# mem.net
KiCad netlist of a schematic drawn in Altium Designer
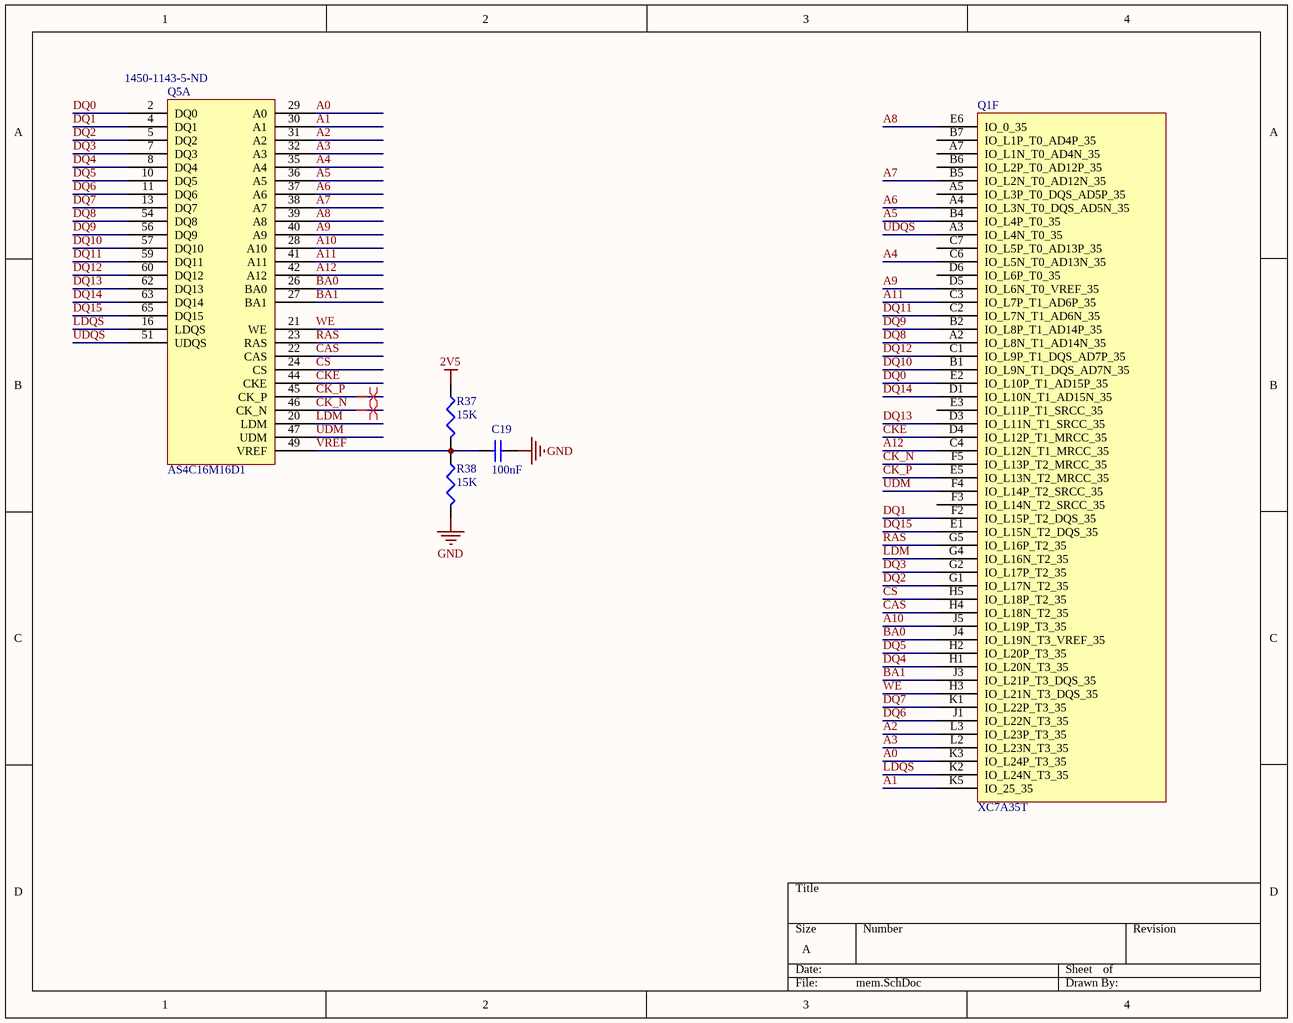
[diagram p0: mem.SchDoc]

(export (version "E")
  (design (tool "Eeschema 10.0.6"))
  (components
    (comp (ref "C19")
      (value "100nF")
      (footprint "CAPC1005X06L")
      (description "Capacitor")
      (fields (field (name "Comment") "Cap") (field (name "PUBLISHER") "Altium Limited"))
      (libsource (lib "Miscellaneous Devices") (part "Cap"))
    )
    (comp (ref "Q1") (value "XC7A35T") (libsource (lib "schlib") (part "XC7A35T")))
    (comp (ref "Q5")
      (value "AS4C16M16D1")
      (footprint "TSOP65P1180X120-66N")
      (fields (field (name "SUPPLIER PART NUMBER 1") "1450-1143-5-ND"))
      (libsource (lib "schlib") (part "DDR256"))
    )
    (comp (ref "R37")
      (value "15K")
      (footprint "CAPC1608X90N")
      (description "Resistor")
      (fields (field (name "Comment") "Res3") (field (name "PUBLISHER") "Altium Limited"))
      (libsource (lib "Miscellaneous Devices") (part "Res3"))
    )
    (comp (ref "R38")
      (value "15K")
      (footprint "CAPC1608X90N")
      (description "Resistor")
      (fields (field (name "Comment") "Res3") (field (name "PUBLISHER") "Altium Limited"))
      (libsource (lib "Miscellaneous Devices") (part "Res3"))
    )
  )
  (nets
    (net (code "1") (name "/A0") (class "Default")
      (node (ref "Q1") (pin "K3") (pinfunction "IO_L24P_T3_35_K3") (pintype "passive"))
      (node (ref "Q5") (pin "29") (pinfunction "A0_29") (pintype "passive"))
    )
    (net (code "2") (name "/A1") (class "Default")
      (node (ref "Q1") (pin "K5") (pinfunction "IO_25_35_K5") (pintype "passive"))
      (node (ref "Q5") (pin "30") (pinfunction "A1_30") (pintype "passive"))
    )
    (net (code "3") (name "/A2") (class "Default")
      (node (ref "Q1") (pin "L3") (pinfunction "IO_L23P_T3_35_L3") (pintype "passive"))
      (node (ref "Q5") (pin "31") (pinfunction "A2_31") (pintype "passive"))
    )
    (net (code "4") (name "/A3") (class "Default")
      (node (ref "Q1") (pin "L2") (pinfunction "IO_L23N_T3_35_L2") (pintype "passive"))
      (node (ref "Q5") (pin "32") (pinfunction "A3_32") (pintype "passive"))
    )
    (net (code "5") (name "/A4") (class "Default")
      (node (ref "Q1") (pin "C6") (pinfunction "IO_L5N_T0_AD13N_35_C6") (pintype "passive"))
      (node (ref "Q5") (pin "35") (pinfunction "A4_35") (pintype "passive"))
    )
    (net (code "6") (name "/A5") (class "Default")
      (node (ref "Q1") (pin "B4") (pinfunction "IO_L4P_T0_35_B4") (pintype "passive"))
      (node (ref "Q5") (pin "36") (pinfunction "A5_36") (pintype "passive"))
    )
    (net (code "7") (name "/A6") (class "Default")
      (node (ref "Q1") (pin "A4") (pinfunction "IO_L3N_T0_DQS_AD5N_35_A4") (pintype "passive"))
      (node (ref "Q5") (pin "37") (pinfunction "A6_37") (pintype "passive"))
    )
    (net (code "8") (name "/A7") (class "Default")
      (node (ref "Q1") (pin "B5") (pinfunction "IO_L2N_T0_AD12N_35_B5") (pintype "passive"))
      (node (ref "Q5") (pin "38") (pinfunction "A7_38") (pintype "passive"))
    )
    (net (code "9") (name "/A8") (class "Default")
      (node (ref "Q1") (pin "E6") (pinfunction "IO_0_35_E6") (pintype "passive"))
      (node (ref "Q5") (pin "39") (pinfunction "A8_39") (pintype "passive"))
    )
    (net (code "10") (name "/A9") (class "Default")
      (node (ref "Q1") (pin "D5") (pinfunction "IO_L6N_T0_VREF_35_D5") (pintype "passive"))
      (node (ref "Q5") (pin "40") (pinfunction "A9_40") (pintype "passive"))
    )
    (net (code "11") (name "/A10") (class "Default")
      (node (ref "Q1") (pin "J5") (pinfunction "IO_L19P_T3_35_J5") (pintype "passive"))
      (node (ref "Q5") (pin "28") (pinfunction "A10_28") (pintype "passive"))
    )
    (net (code "12") (name "/A11") (class "Default")
      (node (ref "Q1") (pin "C3") (pinfunction "IO_L7P_T1_AD6P_35_C3") (pintype "passive"))
      (node (ref "Q5") (pin "41") (pinfunction "A11_41") (pintype "passive"))
    )
    (net (code "13") (name "/A12") (class "Default")
      (node (ref "Q1") (pin "C4") (pinfunction "IO_L12N_T1_MRCC_35_C4") (pintype "passive"))
      (node (ref "Q5") (pin "42") (pinfunction "A12_42") (pintype "passive"))
    )
    (net (code "14") (name "/BA0") (class "Default")
      (node (ref "Q1") (pin "J4") (pinfunction "IO_L19N_T3_VREF_35_J4") (pintype "passive"))
      (node (ref "Q5") (pin "26") (pinfunction "BA0_26") (pintype "passive"))
    )
    (net (code "15") (name "/BA1") (class "Default")
      (node (ref "Q1") (pin "J3") (pinfunction "IO_L21P_T3_DQS_35_J3") (pintype "passive"))
      (node (ref "Q5") (pin "27") (pinfunction "BA1_27") (pintype "passive"))
    )
    (net (code "16") (name "/CAS") (class "Default")
      (node (ref "Q1") (pin "H4") (pinfunction "IO_L18N_T2_35_H4") (pintype "passive"))
      (node (ref "Q5") (pin "22") (pinfunction "CAS_22") (pintype "passive"))
    )
    (net (code "17") (name "/CKE") (class "Default")
      (node (ref "Q1") (pin "D4") (pinfunction "IO_L12P_T1_MRCC_35_D4") (pintype "passive"))
      (node (ref "Q5") (pin "44") (pinfunction "CKE_44") (pintype "passive"))
    )
    (net (code "18") (name "/CK_N") (class "Default")
      (node (ref "Q1") (pin "F5") (pinfunction "IO_L13P_T2_MRCC_35_F5") (pintype "passive"))
      (node (ref "Q5") (pin "46") (pinfunction "CK_N_46") (pintype "passive"))
    )
    (net (code "19") (name "/CK_P") (class "Default")
      (node (ref "Q1") (pin "E5") (pinfunction "IO_L13N_T2_MRCC_35_E5") (pintype "passive"))
      (node (ref "Q5") (pin "45") (pinfunction "CK_P_45") (pintype "passive"))
    )
    (net (code "20") (name "/CS") (class "Default")
      (node (ref "Q1") (pin "H5") (pinfunction "IO_L18P_T2_35_H5") (pintype "passive"))
      (node (ref "Q5") (pin "24") (pinfunction "CS_24") (pintype "passive"))
    )
    (net (code "21") (name "/DQ0") (class "Default")
      (node (ref "Q1") (pin "E2") (pinfunction "IO_L10P_T1_AD15P_35_E2") (pintype "passive"))
      (node (ref "Q5") (pin "2") (pinfunction "DQ0_2") (pintype "passive"))
    )
    (net (code "22") (name "/DQ1") (class "Default")
      (node (ref "Q1") (pin "F2") (pinfunction "IO_L15P_T2_DQS_35_F2") (pintype "passive"))
      (node (ref "Q5") (pin "4") (pinfunction "DQ1_4") (pintype "passive"))
    )
    (net (code "23") (name "/DQ2") (class "Default")
      (node (ref "Q1") (pin "G1") (pinfunction "IO_L17N_T2_35_G1") (pintype "passive"))
      (node (ref "Q5") (pin "5") (pinfunction "DQ2_5") (pintype "passive"))
    )
    (net (code "24") (name "/DQ3") (class "Default")
      (node (ref "Q1") (pin "G2") (pinfunction "IO_L17P_T2_35_G2") (pintype "passive"))
      (node (ref "Q5") (pin "7") (pinfunction "DQ3_7") (pintype "passive"))
    )
    (net (code "25") (name "/DQ4") (class "Default")
      (node (ref "Q1") (pin "H1") (pinfunction "IO_L20N_T3_35_H1") (pintype "passive"))
      (node (ref "Q5") (pin "8") (pinfunction "DQ4_8") (pintype "passive"))
    )
    (net (code "26") (name "/DQ5") (class "Default")
      (node (ref "Q1") (pin "H2") (pinfunction "IO_L20P_T3_35_H2") (pintype "passive"))
      (node (ref "Q5") (pin "10") (pinfunction "DQ5_10") (pintype "passive"))
    )
    (net (code "27") (name "/DQ6") (class "Default")
      (node (ref "Q1") (pin "J1") (pinfunction "IO_L22N_T3_35_J1") (pintype "passive"))
      (node (ref "Q5") (pin "11") (pinfunction "DQ6_11") (pintype "passive"))
    )
    (net (code "28") (name "/DQ7") (class "Default")
      (node (ref "Q1") (pin "K1") (pinfunction "IO_L22P_T3_35_K1") (pintype "passive"))
      (node (ref "Q5") (pin "13") (pinfunction "DQ7_13") (pintype "passive"))
    )
    (net (code "29") (name "/DQ8") (class "Default")
      (node (ref "Q1") (pin "A2") (pinfunction "IO_L8N_T1_AD14N_35_A2") (pintype "passive"))
      (node (ref "Q5") (pin "54") (pinfunction "DQ8_54") (pintype "passive"))
    )
    (net (code "30") (name "/DQ9") (class "Default")
      (node (ref "Q1") (pin "B2") (pinfunction "IO_L8P_T1_AD14P_35_B2") (pintype "passive"))
      (node (ref "Q5") (pin "56") (pinfunction "DQ9_56") (pintype "passive"))
    )
    (net (code "31") (name "/DQ10") (class "Default")
      (node (ref "Q1") (pin "B1") (pinfunction "IO_L9N_T1_DQS_AD7N_35_B1") (pintype "passive"))
      (node (ref "Q5") (pin "57") (pinfunction "DQ10_57") (pintype "passive"))
    )
    (net (code "32") (name "/DQ11") (class "Default")
      (node (ref "Q1") (pin "C2") (pinfunction "IO_L7N_T1_AD6N_35_C2") (pintype "passive"))
      (node (ref "Q5") (pin "59") (pinfunction "DQ11_59") (pintype "passive"))
    )
    (net (code "33") (name "/DQ12") (class "Default")
      (node (ref "Q1") (pin "C1") (pinfunction "IO_L9P_T1_DQS_AD7P_35_C1") (pintype "passive"))
      (node (ref "Q5") (pin "60") (pinfunction "DQ12_60") (pintype "passive"))
    )
    (net (code "34") (name "/DQ13") (class "Default")
      (node (ref "Q1") (pin "D3") (pinfunction "IO_L11N_T1_SRCC_35_D3") (pintype "passive"))
      (node (ref "Q5") (pin "62") (pinfunction "DQ13_62") (pintype "passive"))
    )
    (net (code "35") (name "/DQ14") (class "Default")
      (node (ref "Q1") (pin "D1") (pinfunction "IO_L10N_T1_AD15N_35_D1") (pintype "passive"))
      (node (ref "Q5") (pin "63") (pinfunction "DQ14_63") (pintype "passive"))
    )
    (net (code "36") (name "/DQ15") (class "Default")
      (node (ref "Q1") (pin "E1") (pinfunction "IO_L15N_T2_DQS_35_E1") (pintype "passive"))
      (node (ref "Q5") (pin "65") (pinfunction "DQ15_65") (pintype "passive"))
    )
    (net (code "37") (name "/LDM") (class "Default")
      (node (ref "Q1") (pin "G4") (pinfunction "IO_L16N_T2_35_G4") (pintype "passive"))
      (node (ref "Q5") (pin "20") (pinfunction "LDM_20") (pintype "passive"))
    )
    (net (code "38") (name "/LDQS") (class "Default")
      (node (ref "Q1") (pin "K2") (pinfunction "IO_L24N_T3_35_K2") (pintype "passive"))
      (node (ref "Q5") (pin "16") (pinfunction "LDQS_16") (pintype "passive"))
    )
    (net (code "39") (name "/RAS") (class "Default")
      (node (ref "Q1") (pin "G5") (pinfunction "IO_L16P_T2_35_G5") (pintype "passive"))
      (node (ref "Q5") (pin "23") (pinfunction "RAS_23") (pintype "passive"))
    )
    (net (code "40") (name "/UDM") (class "Default")
      (node (ref "Q1") (pin "F4") (pinfunction "IO_L14P_T2_SRCC_35_F4") (pintype "passive"))
      (node (ref "Q5") (pin "47") (pinfunction "UDM_47") (pintype "passive"))
    )
    (net (code "41") (name "/UDQS") (class "Default")
      (node (ref "Q1") (pin "A3") (pinfunction "IO_L4N_T0_35_A3") (pintype "passive"))
      (node (ref "Q5") (pin "51") (pinfunction "UDQS_51") (pintype "passive"))
    )
    (net (code "42") (name "/VREF") (class "Default")
      (node (ref "C19") (pin "1") (pinfunction "1_1") (pintype "passive"))
      (node (ref "Q5") (pin "49") (pinfunction "VREF_49") (pintype "passive"))
      (node (ref "R37") (pin "2") (pinfunction "2_2") (pintype "passive"))
      (node (ref "R38") (pin "1") (pinfunction "1_1") (pintype "passive"))
    )
    (net (code "43") (name "/WE") (class "Default")
      (node (ref "Q1") (pin "H3") (pinfunction "IO_L21N_T3_DQS_35_H3") (pintype "passive"))
      (node (ref "Q5") (pin "21") (pinfunction "WE_21") (pintype "passive"))
    )
    (net (code "44") (name "2V5") (class "Default")
      (node (ref "R37") (pin "1") (pinfunction "1_1") (pintype "passive"))
    )
    (net (code "45") (name "GND") (class "Default")
      (node (ref "C19") (pin "2") (pinfunction "2_2") (pintype "passive"))
      (node (ref "R38") (pin "2") (pinfunction "2_2") (pintype "passive"))
    )
    (net (code "46") (name "unconnected-(Q1F-IO_L1N_T0_AD4N_35-PadA7)") (class "Default")
      (node (ref "Q1") (pin "A7") (pinfunction "IO_L1N_T0_AD4N_35_A7") (pintype "passive"))
    )
    (net (code "47") (name "unconnected-(Q1F-IO_L1P_T0_AD4P_35-PadB7)") (class "Default")
      (node (ref "Q1") (pin "B7") (pinfunction "IO_L1P_T0_AD4P_35_B7") (pintype "passive"))
    )
    (net (code "48") (name "unconnected-(Q1F-IO_L2P_T0_AD12P_35-PadB6)") (class "Default")
      (node (ref "Q1") (pin "B6") (pinfunction "IO_L2P_T0_AD12P_35_B6") (pintype "passive"))
    )
    (net (code "49") (name "unconnected-(Q1F-IO_L3P_T0_DQS_AD5P_35-PadA5)") (class "Default")
      (node (ref "Q1") (pin "A5") (pinfunction "IO_L3P_T0_DQS_AD5P_35_A5") (pintype "passive"))
    )
    (net (code "50") (name "unconnected-(Q1F-IO_L5P_T0_AD13P_35-PadC7)") (class "Default")
      (node (ref "Q1") (pin "C7") (pinfunction "IO_L5P_T0_AD13P_35_C7") (pintype "passive"))
    )
    (net (code "51") (name "unconnected-(Q1F-IO_L6P_T0_35-PadD6)") (class "Default")
      (node (ref "Q1") (pin "D6") (pinfunction "IO_L6P_T0_35_D6") (pintype "passive"))
    )
    (net (code "52") (name "unconnected-(Q1F-IO_L11P_T1_SRCC_35-PadE3)") (class "Default")
      (node (ref "Q1") (pin "E3") (pinfunction "IO_L11P_T1_SRCC_35_E3") (pintype "passive"))
    )
    (net (code "53") (name "unconnected-(Q1F-IO_L14N_T2_SRCC_35-PadF3)") (class "Default")
      (node (ref "Q1") (pin "F3") (pinfunction "IO_L14N_T2_SRCC_35_F3") (pintype "passive"))
    )
  )
)
